# rs485_transceiver.net
KiCad netlist of a schematic drawn in Altium Designer
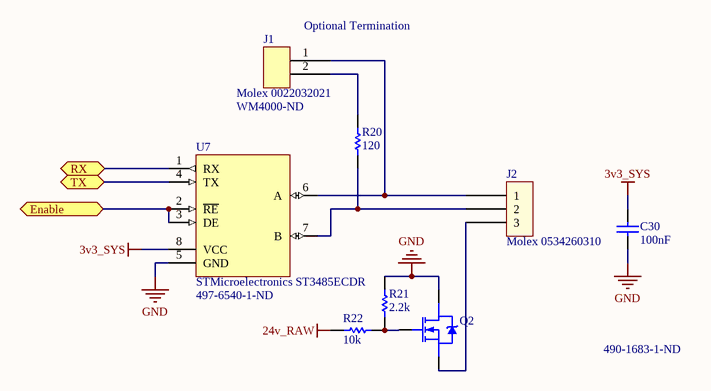
[diagram p0: rs485_transceiver.SchDoc]

(export (version "E")
  (design (tool "Eeschema 10.0.6"))
  (components
    (comp (ref "C30")
      (value "Murata GRM219R71C104KA01D")
      (footprint "PCB-3a53f7g8nqmmfsudd9tf-1")
      (description "0805 0.1 uF 16 V ±10 % Tolerance X7R Surface Mount Multilayer Ceramic Capacitor")
      (fields
        (field (name "CAPACITANCE") "100nF")
        (field (name "MANUFACTURER PART NUMBER") "GRM219R71C104KA01D")
      )
      (libsource (lib "CommunityVault") (part "CMP-f3963a9e29dd2c51-2"))
    )
    (comp (ref "J1")
      (value "Molex 0022032021")
      (footprint "PCB-ayp4uy6mce3kuznu7cpv-1")
      (fields (field (name "MANUFACTURER PART NUMBER") "0022032021"))
      (libsource (lib "CommunityVault") (part "SYM-db3d12a8237904fa-1"))
    )
    (comp (ref "J2")
      (value "Molex 0534260310")
      (footprint "PCB-uh5qjayc3e5325ry13yq-1")
      (description "Conn Shrouded Header HDR 3 POS 2.5mm Solder RA Thru-Hole Mini-Lock™ Tray")
      (libsource (lib "CommunityVault") (part "CMP-86e74f44d2545920-1"))
    )
    (comp (ref "Q2")
      (value "2N7002P")
      (footprint "Nexperia 2n7002P")
      (description "N-Channel 60 V 1.6 Ohm 350 mW 0.8 nC Surface Mount TrenchMOS FET - SOT-23")
      (fields (field (name "MANUFACTURER PART NUMBER") "2N7002P,215"))
      (libsource (lib "CommunityVault") (part "2N7002P,215"))
    )
    (comp (ref "R20")
      (value "Stackpole Electronics RMCF0603FT120R")
      (footprint "PCB-9ahxsq8gddjqcnfjmojj-1")
      (fields (field (name "MANUFACTURER PART NUMBER") "RMCF0603FT120R") (field (name "RESISTANCE") "120"))
      (libsource (lib "CommunityVault") (part "CMP-7038b8177fceafff-1"))
    )
    (comp (ref "R21")
      (value "Stackpole Electronics RMCF0603FT120R")
      (footprint "PCB-9ahxsq8gddjqcnfjmojj-1")
      (fields (field (name "MANUFACTURER PART NUMBER") "RMCF0603FT120R") (field (name "RESISTANCE") "2.2k"))
      (libsource (lib "CommunityVault") (part "CMP-7038b8177fceafff-1"))
    )
    (comp (ref "R22")
      (value "Stackpole Electronics RMCF0603FT120R")
      (footprint "PCB-9ahxsq8gddjqcnfjmojj-1")
      (fields (field (name "MANUFACTURER PART NUMBER") "RMCF0603FT120R") (field (name "RESISTANCE") "10k"))
      (libsource (lib "CommunityVault") (part "CMP-7038b8177fceafff-1"))
    )
    (comp (ref "U7")
      (value "STMicroelectronics ST3485ECDR")
      (footprint "PCB-lmrwxhl2h1q3b67kej26-1")
      (description "ST3485E Series 3.3 V ±15 kV ESD Protected RS-485/RS-422 Transceiver - SOIC-8")
      (fields (field (name "MANUFACTURER PART NUMBER") "ST3485ECDR"))
      (libsource (lib "CommunityVault") (part "SYM-4f81868cdec19046-1"))
    )
  )
  (nets
    (net (code "1") (name "/Enable") (class "Default")
      (node (ref "U7") (pin "2") (pinfunction "~{RE}_2") (pintype "input"))
      (node (ref "U7") (pin "3") (pinfunction "DE_3") (pintype "input"))
    )
    (net (code "2") (name "/RX") (class "Default")
      (node (ref "U7") (pin "1") (pinfunction "RX_1") (pintype "output"))
    )
    (net (code "3") (name "/TX") (class "Default")
      (node (ref "U7") (pin "4") (pinfunction "TX_4") (pintype "input"))
    )
    (net (code "4") (name "3v3_SYS") (class "Default")
      (node (ref "C30") (pin "1") (pinfunction "1_1") (pintype "passive"))
      (node (ref "U7") (pin "8") (pinfunction "VCC_8") (pintype "power_in"))
    )
    (net (code "5") (name "24v_RAW") (class "Default")
      (node (ref "R22") (pin "1") (pinfunction "1_1") (pintype "passive"))
    )
    (net (code "6") (name "GND") (class "Default")
      (node (ref "C30") (pin "2") (pinfunction "2_2") (pintype "passive"))
      (node (ref "Q2") (pin "3") (pinfunction "D_3") (pintype "passive"))
      (node (ref "R21") (pin "1") (pinfunction "1_1") (pintype "passive"))
      (node (ref "U7") (pin "5") (pinfunction "GND_5") (pintype "power_in"))
    )
    (net (code "7") (name "Net-(J1-1-Pad2)") (class "Default")
      (node (ref "J1") (pin "2") (pinfunction "1_2") (pintype "passive"))
      (node (ref "R20") (pin "2") (pinfunction "2_2") (pintype "passive"))
    )
    (net (code "8") (name "Net-(Q2-G)") (class "Default")
      (node (ref "Q2") (pin "1") (pinfunction "G_1") (pintype "passive"))
      (node (ref "R21") (pin "2") (pinfunction "2_2") (pintype "passive"))
      (node (ref "R22") (pin "2") (pinfunction "2_2") (pintype "passive"))
    )
    (net (code "9") (name "Net-(Q2-S)") (class "Default")
      (node (ref "J2") (pin "3") (pinfunction "3_3") (pintype "passive"))
      (node (ref "Q2") (pin "2") (pinfunction "S_2") (pintype "passive"))
    )
    (net (code "10") (name "Net-(U7-A)") (class "Default")
      (node (ref "J1") (pin "1") (pinfunction "1_1") (pintype "passive"))
      (node (ref "J2") (pin "1") (pinfunction "1_1") (pintype "passive"))
      (node (ref "U7") (pin "6") (pinfunction "A_6") (pintype "bidirectional"))
    )
    (net (code "11") (name "Net-(U7-B)") (class "Default")
      (node (ref "J2") (pin "2") (pinfunction "2_2") (pintype "passive"))
      (node (ref "R20") (pin "1") (pinfunction "1_1") (pintype "passive"))
      (node (ref "U7") (pin "7") (pinfunction "B_7") (pintype "bidirectional"))
    )
  )
)
